# 3_ADSTM32_Peripheral.net
KiCad netlist of a schematic drawn in Altium Designer
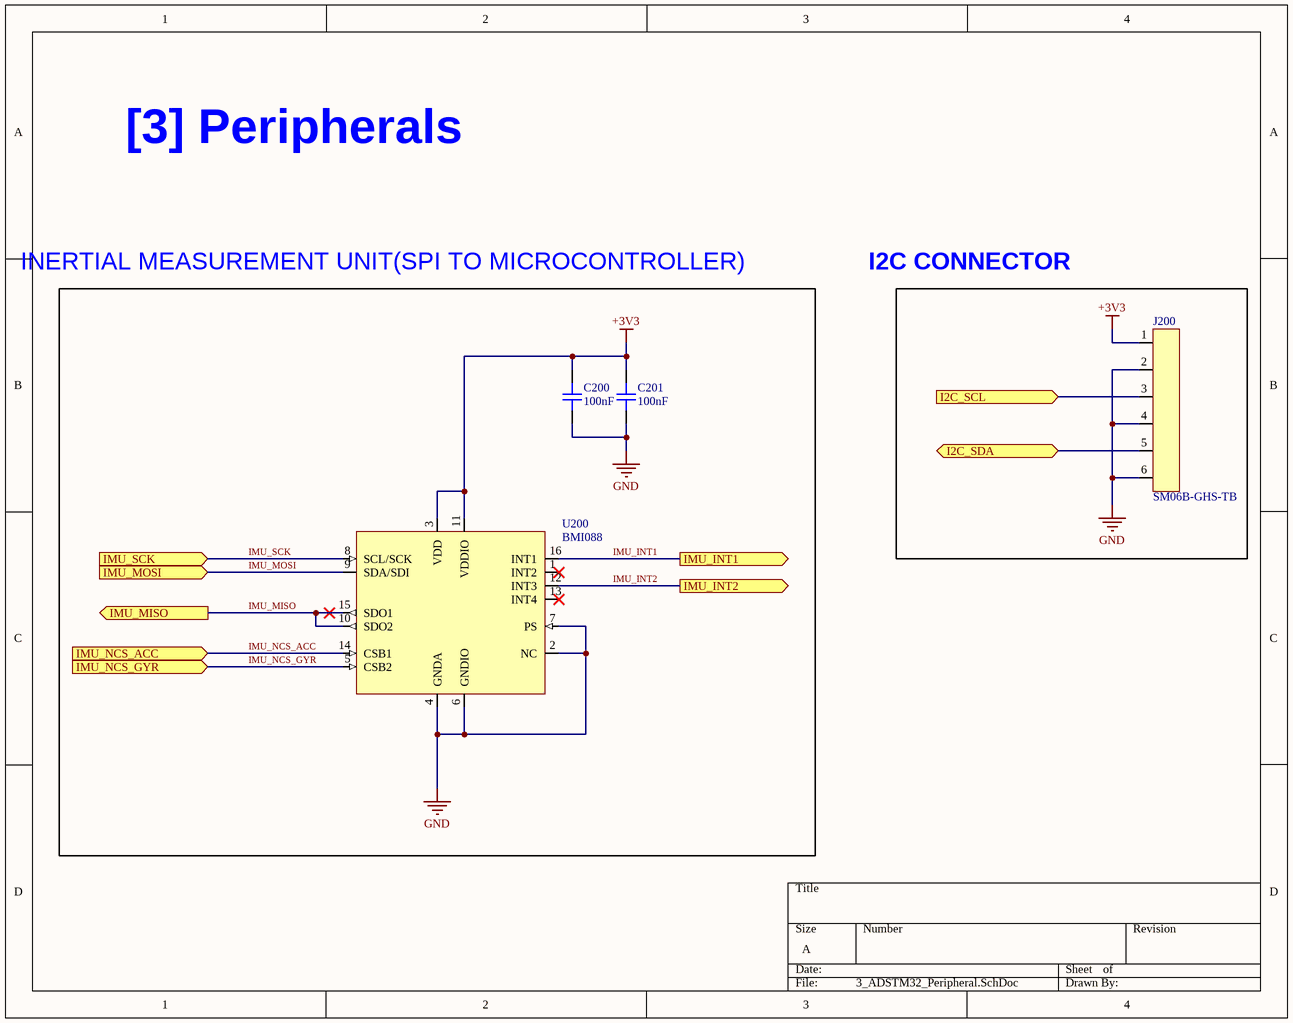
[diagram p0: 3_ADSTM32_Peripheral.SchDoc]

(export (version "E")
  (design (tool "Eeschema 10.0.6"))
  (components
    (comp (ref "C200")
      (value "100nF")
      (footprint "CAP_0603")
      (description "Capacitor SMD 0603 16V")
      (libsource (lib "Schematic-Lib-PhilsLab") (part "CAP_0603_16V"))
    )
    (comp (ref "C201")
      (value "100nF")
      (footprint "CAP_0603")
      (description "Capacitor SMD 0603 16V")
      (libsource (lib "Schematic-Lib-PhilsLab") (part "CAP_0603_16V"))
    )
    (comp (ref "J200")
      (value "SM06B-GHS-TB")
      (footprint "SM06B-GHS-TB")
      (description "Header Connector 6 Position 1.25MM Pitch SMD Horizontal JST GH")
      (fields (field (name "MANUFACTURER") "JST"))
      (libsource (lib "Schematic-Lib-PhilsLab") (part "SM06B-GHS-TB"))
    )
    (comp (ref "U200")
      (value "BMI088")
      (footprint "BMI088")
      (description "Inertial Measurement Unit IMU 6-Axis LGA")
      (fields (field (name "MANUFACTURER") "Bosch"))
      (libsource (lib "Schematic-Lib-PhilsLab") (part "BMI088"))
    )
  )
  (nets
    (net (code "1") (name "+3V3") (class "Default")
      (node (ref "C200") (pin "2") (pinfunction "2_2") (pintype "passive"))
      (node (ref "C201") (pin "2") (pinfunction "2_2") (pintype "passive"))
      (node (ref "J200") (pin "1") (pinfunction "1_1") (pintype "passive"))
      (node (ref "U200") (pin "11") (pinfunction "VDDIO_11") (pintype "power_in"))
      (node (ref "U200") (pin "3") (pinfunction "VDD_3") (pintype "power_in"))
    )
    (net (code "2") (name "/I2C_SCL") (class "Default")
      (node (ref "J200") (pin "3") (pinfunction "3_3") (pintype "passive"))
    )
    (net (code "3") (name "/I2C_SDA") (class "Default")
      (node (ref "J200") (pin "5") (pinfunction "5_5") (pintype "passive"))
    )
    (net (code "4") (name "/IMU_INT1") (class "Default")
      (node (ref "U200") (pin "16") (pinfunction "INT1_16") (pintype "bidirectional"))
    )
    (net (code "5") (name "/IMU_INT2") (class "Default")
      (node (ref "U200") (pin "12") (pinfunction "INT3_12") (pintype "bidirectional"))
    )
    (net (code "6") (name "/IMU_MISO") (class "Default")
      (node (ref "U200") (pin "10") (pinfunction "SDO2_10") (pintype "output"))
      (node (ref "U200") (pin "15") (pinfunction "SDO1_15") (pintype "output"))
    )
    (net (code "7") (name "/IMU_MOSI") (class "Default")
      (node (ref "U200") (pin "9") (pinfunction "SDA/SDI_9") (pintype "bidirectional"))
    )
    (net (code "8") (name "/IMU_NCS_ACC") (class "Default")
      (node (ref "U200") (pin "14") (pinfunction "CSB1_14") (pintype "input"))
    )
    (net (code "9") (name "/IMU_NCS_GYR") (class "Default")
      (node (ref "U200") (pin "5") (pinfunction "CSB2_5") (pintype "input"))
    )
    (net (code "10") (name "/IMU_SCK") (class "Default")
      (node (ref "U200") (pin "8") (pinfunction "SCL/SCK_8") (pintype "input"))
    )
    (net (code "11") (name "GND") (class "Default")
      (node (ref "C200") (pin "1") (pinfunction "1_1") (pintype "passive"))
      (node (ref "C201") (pin "1") (pinfunction "1_1") (pintype "passive"))
      (node (ref "J200") (pin "2") (pinfunction "2_2") (pintype "passive"))
      (node (ref "J200") (pin "4") (pinfunction "4_4") (pintype "passive"))
      (node (ref "J200") (pin "6") (pinfunction "6_6") (pintype "passive"))
      (node (ref "U200") (pin "2") (pinfunction "NC_2") (pintype "passive"))
      (node (ref "U200") (pin "4") (pinfunction "GNDA_4") (pintype "power_in"))
      (node (ref "U200") (pin "6") (pinfunction "GNDIO_6") (pintype "power_in"))
      (node (ref "U200") (pin "7") (pinfunction "PS_7") (pintype "input"))
    )
    (net (code "12") (name "unconnected-(U200-INT2-Pad1)") (class "Default")
      (node (ref "U200") (pin "1") (pinfunction "INT2_1") (pintype "bidirectional+no_connect"))
    )
    (net (code "13") (name "unconnected-(U200-INT4-Pad13)") (class "Default")
      (node (ref "U200") (pin "13") (pinfunction "INT4_13") (pintype "bidirectional+no_connect"))
    )
  )
)
